# flossjtag.net
KiCad netlist of a schematic drawn in EAGLE
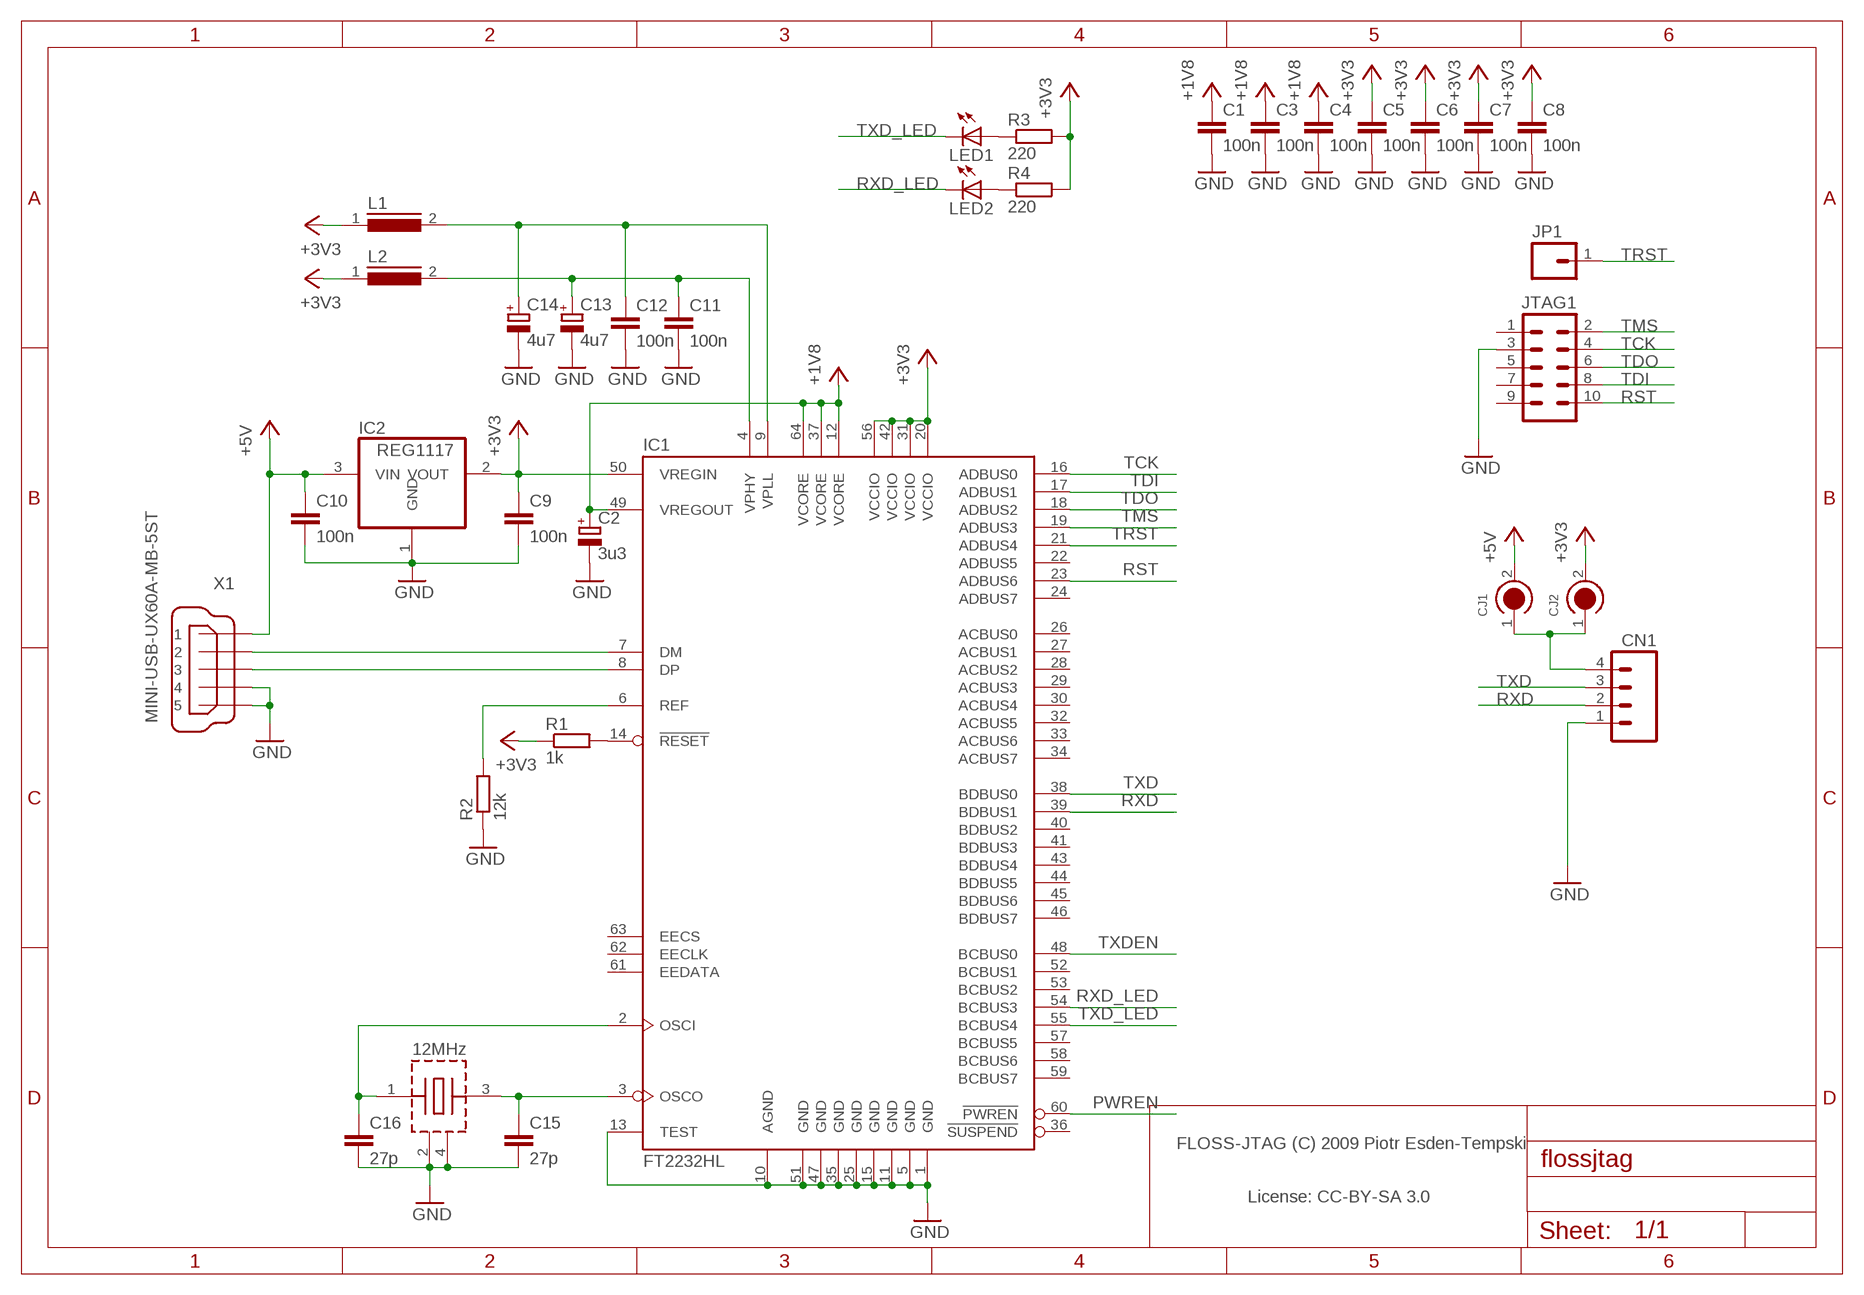
[diagram p0: schematic, sheet 1]

(export (version "E")
  (design (tool "Eeschema 10.0.6"))
  (components
    (comp (ref "C1")
      (value "100n")
      (footprint "eagle-import:C0603")
      (libsource (lib "eagle-import") (part "C-EUC0603"))
    )
    (comp (ref "C2")
      (value "3u3")
      (footprint "eagle-import:A_3216-18R")
      (libsource (lib "eagle-import") (part "CPOL-EUA/3216-18R"))
    )
    (comp (ref "C3")
      (value "100n")
      (footprint "eagle-import:C0603")
      (libsource (lib "eagle-import") (part "C-EUC0603"))
    )
    (comp (ref "C4")
      (value "100n")
      (footprint "eagle-import:C0603")
      (libsource (lib "eagle-import") (part "C-EUC0603"))
    )
    (comp (ref "C5")
      (value "100n")
      (footprint "eagle-import:C0603")
      (libsource (lib "eagle-import") (part "C-EUC0603"))
    )
    (comp (ref "C6")
      (value "100n")
      (footprint "eagle-import:C0603")
      (libsource (lib "eagle-import") (part "C-EUC0603"))
    )
    (comp (ref "C7")
      (value "100n")
      (footprint "eagle-import:C0603")
      (libsource (lib "eagle-import") (part "C-EUC0603"))
    )
    (comp (ref "C8")
      (value "100n")
      (footprint "eagle-import:C0603")
      (libsource (lib "eagle-import") (part "C-EUC0603"))
    )
    (comp (ref "C9")
      (value "100n")
      (footprint "eagle-import:C0603")
      (libsource (lib "eagle-import") (part "C-EUC0603"))
    )
    (comp (ref "C10")
      (value "100n")
      (footprint "eagle-import:C0603")
      (libsource (lib "eagle-import") (part "C-EUC0603"))
    )
    (comp (ref "C11")
      (value "100n")
      (footprint "eagle-import:C0603")
      (libsource (lib "eagle-import") (part "C-EUC0603"))
    )
    (comp (ref "C12")
      (value "100n")
      (footprint "eagle-import:C0603")
      (libsource (lib "eagle-import") (part "C-EUC0603"))
    )
    (comp (ref "C13")
      (value "4u7")
      (footprint "eagle-import:A_3216-18R")
      (libsource (lib "eagle-import") (part "CPOL-EUA/3216-18R"))
    )
    (comp (ref "C14")
      (value "4u7")
      (footprint "eagle-import:A_3216-18R")
      (libsource (lib "eagle-import") (part "CPOL-EUA/3216-18R"))
    )
    (comp (ref "C15")
      (value "27p")
      (footprint "eagle-import:C0603")
      (libsource (lib "eagle-import") (part "C-EUC0603"))
    )
    (comp (ref "C16")
      (value "27p")
      (footprint "eagle-import:C0603")
      (libsource (lib "eagle-import") (part "C-EUC0603"))
    )
    (comp (ref "CJ1")
      (value "CIRC_JMP")
      (footprint "eagle-import:CIRC_JMP")
      (libsource (lib "eagle-import") (part "CIRC_JMP"))
    )
    (comp (ref "CJ2")
      (value "CIRC_JMP")
      (footprint "eagle-import:CIRC_JMP")
      (libsource (lib "eagle-import") (part "CIRC_JMP"))
    )
    (comp (ref "CN1")
      (value "SM04B-SRSS-TB")
      (footprint "eagle-import:SM04B-SRSS-TB")
      (libsource (lib "eagle-import") (part "SM04B-SRSS-TB"))
    )
    (comp (ref "IC1")
      (value "FT2232HL")
      (footprint "eagle-import:LQFP64")
      (libsource (lib "eagle-import") (part "FT2232HL"))
    )
    (comp (ref "IC2")
      (value "REG1117")
      (footprint "eagle-import:SOT223")
      (libsource (lib "eagle-import") (part "REG1117"))
    )
    (comp (ref "JP1")
      (value "PAD-0.06")
      (footprint "eagle-import:PAD-0.06")
      (libsource (lib "eagle-import") (part "PAD-0.06"))
    )
    (comp (ref "JTAG1")
      (value "JTAG-EDGE")
      (footprint "eagle-import:JTAG-EDGE")
      (libsource (lib "eagle-import") (part "JTAG-EDGE"))
    )
    (comp (ref "L1")
      (value "I0603")
      (footprint "eagle-import:R0603")
      (libsource (lib "eagle-import") (part "I0603"))
    )
    (comp (ref "L2")
      (value "I0603")
      (footprint "eagle-import:R0603")
      (libsource (lib "eagle-import") (part "I0603"))
    )
    (comp (ref "LED1")
      (value "LEDCHIP-LED0603")
      (footprint "eagle-import:CHIP-LED0603")
      (libsource (lib "eagle-import") (part "LEDCHIP-LED0603"))
    )
    (comp (ref "LED2")
      (value "LEDCHIP-LED0603")
      (footprint "eagle-import:CHIP-LED0603")
      (libsource (lib "eagle-import") (part "LEDCHIP-LED0603"))
    )
    (comp (ref "R1")
      (value "1k")
      (footprint "eagle-import:R0603")
      (libsource (lib "eagle-import") (part "R-EU_R0603"))
    )
    (comp (ref "R2")
      (value "12k")
      (footprint "eagle-import:R0603")
      (libsource (lib "eagle-import") (part "R-EU_R0603"))
    )
    (comp (ref "R3")
      (value "220")
      (footprint "eagle-import:R0603")
      (libsource (lib "eagle-import") (part "R-EU_R0603"))
    )
    (comp (ref "R4")
      (value "220")
      (footprint "eagle-import:R0603")
      (libsource (lib "eagle-import") (part "R-EU_R0603"))
    )
    (comp (ref "X1")
      (value "MINI-USB-UX60A-MB-5ST")
      (footprint "eagle-import:UX60A-MB-5ST")
      (libsource (lib "eagle-import") (part "MINI-USB-UX60A-MB-5ST"))
    )
    (comp (ref "X3")
      (value "12MHz")
      (footprint "eagle-import:NX3225SA")
      (libsource (lib "eagle-import") (part "NX3225SA"))
    )
  )
  (nets
    (net (code "1") (name "+1V8") (class "Default")
      (node (ref "C1") (pin "1") (pinfunction "1_1") (pintype "passive"))
      (node (ref "C2") (pin "+") (pinfunction "+_+") (pintype "passive"))
      (node (ref "C3") (pin "1") (pinfunction "1_1") (pintype "passive"))
      (node (ref "C4") (pin "1") (pinfunction "1_1") (pintype "passive"))
      (node (ref "IC1") (pin "12") (pinfunction "VCORE_12") (pintype "bidirectional"))
      (node (ref "IC1") (pin "37") (pinfunction "VCORE_37") (pintype "bidirectional"))
      (node (ref "IC1") (pin "49") (pinfunction "VREGOUT_49") (pintype "bidirectional"))
      (node (ref "IC1") (pin "64") (pinfunction "VCORE_64") (pintype "bidirectional"))
    )
    (net (code "2") (name "+3V3") (class "Default")
      (node (ref "C5") (pin "1") (pinfunction "1_1") (pintype "passive"))
      (node (ref "C6") (pin "1") (pinfunction "1_1") (pintype "passive"))
      (node (ref "C7") (pin "1") (pinfunction "1_1") (pintype "passive"))
      (node (ref "C8") (pin "1") (pinfunction "1_1") (pintype "passive"))
      (node (ref "C9") (pin "1") (pinfunction "1_1") (pintype "passive"))
      (node (ref "CJ2") (pin "2") (pinfunction "P$2_2") (pintype "bidirectional"))
      (node (ref "IC1") (pin "20") (pinfunction "VCCIO_20") (pintype "bidirectional"))
      (node (ref "IC1") (pin "31") (pinfunction "VCCIO_31") (pintype "bidirectional"))
      (node (ref "IC1") (pin "42") (pinfunction "VCCIO_42") (pintype "bidirectional"))
      (node (ref "IC1") (pin "50") (pinfunction "VREGIN_50") (pintype "bidirectional"))
      (node (ref "IC1") (pin "56") (pinfunction "VCCIO_56") (pintype "bidirectional"))
      (node (ref "IC2") (pin "2") (pinfunction "VOUT_2") (pintype "output"))
      (node (ref "L1") (pin "1") (pinfunction "1_1") (pintype "passive"))
      (node (ref "L2") (pin "1") (pinfunction "1_1") (pintype "passive"))
      (node (ref "R1") (pin "1") (pinfunction "1_1") (pintype "passive"))
      (node (ref "R3") (pin "2") (pinfunction "2_2") (pintype "passive"))
      (node (ref "R4") (pin "2") (pinfunction "2_2") (pintype "passive"))
    )
    (net (code "3") (name "+5V") (class "Default")
      (node (ref "C10") (pin "1") (pinfunction "1_1") (pintype "passive"))
      (node (ref "CJ1") (pin "2") (pinfunction "P$2_2") (pintype "bidirectional"))
      (node (ref "IC2") (pin "3") (pinfunction "VIN_3") (pintype "input"))
      (node (ref "X1") (pin "1") (pinfunction "1_1") (pintype "input"))
    )
    (net (code "4") (name "/PWREN") (class "Default")
      (node (ref "IC1") (pin "60") (pinfunction "~{PWREN}_60") (pintype "bidirectional"))
    )
    (net (code "5") (name "/RST") (class "Default")
      (node (ref "IC1") (pin "23") (pinfunction "ADBUS6_23") (pintype "bidirectional"))
      (node (ref "JTAG1") (pin "10") (pinfunction "10_10") (pintype "passive"))
    )
    (net (code "6") (name "/RXD") (class "Default")
      (node (ref "CN1") (pin "2") (pinfunction "2_2") (pintype "passive"))
      (node (ref "IC1") (pin "39") (pinfunction "BDBUS1_39") (pintype "bidirectional"))
    )
    (net (code "7") (name "/RXD_LED") (class "Default")
      (node (ref "IC1") (pin "54") (pinfunction "BCBUS3_54") (pintype "bidirectional"))
      (node (ref "LED2") (pin "C") (pinfunction "C_C") (pintype "passive"))
    )
    (net (code "8") (name "/TCK") (class "Default")
      (node (ref "IC1") (pin "16") (pinfunction "ADBUS0_16") (pintype "bidirectional"))
      (node (ref "JTAG1") (pin "4") (pinfunction "4_4") (pintype "passive"))
    )
    (net (code "9") (name "/TDI") (class "Default")
      (node (ref "IC1") (pin "17") (pinfunction "ADBUS1_17") (pintype "bidirectional"))
      (node (ref "JTAG1") (pin "8") (pinfunction "8_8") (pintype "passive"))
    )
    (net (code "10") (name "/TDO") (class "Default")
      (node (ref "IC1") (pin "18") (pinfunction "ADBUS2_18") (pintype "bidirectional"))
      (node (ref "JTAG1") (pin "6") (pinfunction "6_6") (pintype "passive"))
    )
    (net (code "11") (name "/TMS") (class "Default")
      (node (ref "IC1") (pin "19") (pinfunction "ADBUS3_19") (pintype "bidirectional"))
      (node (ref "JTAG1") (pin "2") (pinfunction "2_2") (pintype "passive"))
    )
    (net (code "12") (name "/TRST") (class "Default")
      (node (ref "IC1") (pin "21") (pinfunction "ADBUS4_21") (pintype "bidirectional"))
      (node (ref "JP1") (pin "1") (pinfunction "1_1") (pintype "passive"))
    )
    (net (code "13") (name "/TXD") (class "Default")
      (node (ref "CN1") (pin "3") (pinfunction "3_3") (pintype "passive"))
      (node (ref "IC1") (pin "38") (pinfunction "BDBUS0_38") (pintype "bidirectional"))
    )
    (net (code "14") (name "/TXDEN") (class "Default")
      (node (ref "IC1") (pin "48") (pinfunction "BCBUS0_48") (pintype "bidirectional"))
    )
    (net (code "15") (name "/TXD_LED") (class "Default")
      (node (ref "IC1") (pin "55") (pinfunction "BCBUS4_55") (pintype "bidirectional"))
      (node (ref "LED1") (pin "C") (pinfunction "C_C") (pintype "passive"))
    )
    (net (code "16") (name "GND") (class "Default")
      (node (ref "C1") (pin "2") (pinfunction "2_2") (pintype "passive"))
      (node (ref "C10") (pin "2") (pinfunction "2_2") (pintype "passive"))
      (node (ref "C11") (pin "2") (pinfunction "2_2") (pintype "passive"))
      (node (ref "C12") (pin "2") (pinfunction "2_2") (pintype "passive"))
      (node (ref "C13") (pin "-") (pinfunction "-_-") (pintype "passive"))
      (node (ref "C14") (pin "-") (pinfunction "-_-") (pintype "passive"))
      (node (ref "C15") (pin "2") (pinfunction "2_2") (pintype "passive"))
      (node (ref "C16") (pin "2") (pinfunction "2_2") (pintype "passive"))
      (node (ref "C2") (pin "-") (pinfunction "-_-") (pintype "passive"))
      (node (ref "C3") (pin "2") (pinfunction "2_2") (pintype "passive"))
      (node (ref "C4") (pin "2") (pinfunction "2_2") (pintype "passive"))
      (node (ref "C5") (pin "2") (pinfunction "2_2") (pintype "passive"))
      (node (ref "C6") (pin "2") (pinfunction "2_2") (pintype "passive"))
      (node (ref "C7") (pin "2") (pinfunction "2_2") (pintype "passive"))
      (node (ref "C8") (pin "2") (pinfunction "2_2") (pintype "passive"))
      (node (ref "C9") (pin "2") (pinfunction "2_2") (pintype "passive"))
      (node (ref "CN1") (pin "1") (pinfunction "1_1") (pintype "passive"))
      (node (ref "IC1") (pin "1") (pinfunction "GND_1") (pintype "bidirectional"))
      (node (ref "IC1") (pin "10") (pinfunction "AGND_10") (pintype "bidirectional"))
      (node (ref "IC1") (pin "11") (pinfunction "GND_11") (pintype "bidirectional"))
      (node (ref "IC1") (pin "13") (pinfunction "TEST_13") (pintype "bidirectional"))
      (node (ref "IC1") (pin "15") (pinfunction "GND_15") (pintype "bidirectional"))
      (node (ref "IC1") (pin "25") (pinfunction "GND_25") (pintype "bidirectional"))
      (node (ref "IC1") (pin "35") (pinfunction "GND_35") (pintype "bidirectional"))
      (node (ref "IC1") (pin "47") (pinfunction "GND_47") (pintype "bidirectional"))
      (node (ref "IC1") (pin "5") (pinfunction "GND_5") (pintype "bidirectional"))
      (node (ref "IC1") (pin "51") (pinfunction "GND_51") (pintype "bidirectional"))
      (node (ref "IC2") (pin "1") (pinfunction "GND_1") (pintype "power_in"))
      (node (ref "JTAG1") (pin "3") (pinfunction "3_3") (pintype "passive"))
      (node (ref "R2") (pin "1") (pinfunction "1_1") (pintype "passive"))
      (node (ref "X1") (pin "4") (pinfunction "4_4") (pintype "input"))
      (node (ref "X1") (pin "5") (pinfunction "5_5") (pintype "input"))
      (node (ref "X3") (pin "2") (pinfunction "GND_2") (pintype "bidirectional"))
      (node (ref "X3") (pin "4") (pinfunction "GND_4") (pintype "bidirectional"))
    )
    (net (code "17") (name "Net-(CJ1-P$1)") (class "Default")
      (node (ref "CJ1") (pin "1") (pinfunction "P$1_1") (pintype "bidirectional"))
      (node (ref "CJ2") (pin "1") (pinfunction "P$1_1") (pintype "bidirectional"))
      (node (ref "CN1") (pin "4") (pinfunction "4_4") (pintype "passive"))
    )
    (net (code "18") (name "Net-(IC1-DM)") (class "Default")
      (node (ref "IC1") (pin "7") (pinfunction "DM_7") (pintype "bidirectional"))
      (node (ref "X1") (pin "2") (pinfunction "2_2") (pintype "input"))
    )
    (net (code "19") (name "Net-(IC1-DP)") (class "Default")
      (node (ref "IC1") (pin "8") (pinfunction "DP_8") (pintype "bidirectional"))
      (node (ref "X1") (pin "3") (pinfunction "3_3") (pintype "input"))
    )
    (net (code "20") (name "Net-(IC1-OSCI)") (class "Default")
      (node (ref "C16") (pin "1") (pinfunction "1_1") (pintype "passive"))
      (node (ref "IC1") (pin "2") (pinfunction "OSCI_2") (pintype "bidirectional"))
      (node (ref "X3") (pin "1") (pinfunction "XTAL_1") (pintype "bidirectional"))
    )
    (net (code "21") (name "Net-(IC1-OSCO)") (class "Default")
      (node (ref "C15") (pin "1") (pinfunction "1_1") (pintype "passive"))
      (node (ref "IC1") (pin "3") (pinfunction "OSCO_3") (pintype "bidirectional"))
      (node (ref "X3") (pin "3") (pinfunction "XTAL_3") (pintype "bidirectional"))
    )
    (net (code "22") (name "Net-(IC1-REF)") (class "Default")
      (node (ref "IC1") (pin "6") (pinfunction "REF_6") (pintype "bidirectional"))
      (node (ref "R2") (pin "2") (pinfunction "2_2") (pintype "passive"))
    )
    (net (code "23") (name "Net-(IC1-VPHY)") (class "Default")
      (node (ref "C11") (pin "1") (pinfunction "1_1") (pintype "passive"))
      (node (ref "C13") (pin "+") (pinfunction "+_+") (pintype "passive"))
      (node (ref "IC1") (pin "4") (pinfunction "VPHY_4") (pintype "bidirectional"))
      (node (ref "L2") (pin "2") (pinfunction "2_2") (pintype "passive"))
    )
    (net (code "24") (name "Net-(IC1-VPLL)") (class "Default")
      (node (ref "C12") (pin "1") (pinfunction "1_1") (pintype "passive"))
      (node (ref "C14") (pin "+") (pinfunction "+_+") (pintype "passive"))
      (node (ref "IC1") (pin "9") (pinfunction "VPLL_9") (pintype "bidirectional"))
      (node (ref "L1") (pin "2") (pinfunction "2_2") (pintype "passive"))
    )
    (net (code "25") (name "Net-(IC1-~{RESET})") (class "Default")
      (node (ref "IC1") (pin "14") (pinfunction "~{RESET}_14") (pintype "bidirectional"))
      (node (ref "R1") (pin "2") (pinfunction "2_2") (pintype "passive"))
    )
    (net (code "26") (name "Net-(LED1-PadA)") (class "Default")
      (node (ref "LED1") (pin "A") (pinfunction "A_A") (pintype "passive"))
      (node (ref "R3") (pin "1") (pinfunction "1_1") (pintype "passive"))
    )
    (net (code "27") (name "Net-(LED2-PadA)") (class "Default")
      (node (ref "LED2") (pin "A") (pinfunction "A_A") (pintype "passive"))
      (node (ref "R4") (pin "1") (pinfunction "1_1") (pintype "passive"))
    )
    (net (code "28") (name "unconnected-(IC1-ACBUS0-Pad26)") (class "Default")
      (node (ref "IC1") (pin "26") (pinfunction "ACBUS0_26") (pintype "bidirectional"))
    )
    (net (code "29") (name "unconnected-(IC1-ACBUS1-Pad27)") (class "Default")
      (node (ref "IC1") (pin "27") (pinfunction "ACBUS1_27") (pintype "bidirectional"))
    )
    (net (code "30") (name "unconnected-(IC1-ACBUS2-Pad28)") (class "Default")
      (node (ref "IC1") (pin "28") (pinfunction "ACBUS2_28") (pintype "bidirectional"))
    )
    (net (code "31") (name "unconnected-(IC1-ACBUS3-Pad29)") (class "Default")
      (node (ref "IC1") (pin "29") (pinfunction "ACBUS3_29") (pintype "bidirectional"))
    )
    (net (code "32") (name "unconnected-(IC1-ACBUS4-Pad30)") (class "Default")
      (node (ref "IC1") (pin "30") (pinfunction "ACBUS4_30") (pintype "bidirectional"))
    )
    (net (code "33") (name "unconnected-(IC1-ACBUS5-Pad32)") (class "Default")
      (node (ref "IC1") (pin "32") (pinfunction "ACBUS5_32") (pintype "bidirectional"))
    )
    (net (code "34") (name "unconnected-(IC1-ACBUS6-Pad33)") (class "Default")
      (node (ref "IC1") (pin "33") (pinfunction "ACBUS6_33") (pintype "bidirectional"))
    )
    (net (code "35") (name "unconnected-(IC1-ACBUS7-Pad34)") (class "Default")
      (node (ref "IC1") (pin "34") (pinfunction "ACBUS7_34") (pintype "bidirectional"))
    )
    (net (code "36") (name "unconnected-(IC1-ADBUS5-Pad22)") (class "Default")
      (node (ref "IC1") (pin "22") (pinfunction "ADBUS5_22") (pintype "bidirectional"))
    )
    (net (code "37") (name "unconnected-(IC1-ADBUS7-Pad24)") (class "Default")
      (node (ref "IC1") (pin "24") (pinfunction "ADBUS7_24") (pintype "bidirectional"))
    )
    (net (code "38") (name "unconnected-(IC1-BCBUS1-Pad52)") (class "Default")
      (node (ref "IC1") (pin "52") (pinfunction "BCBUS1_52") (pintype "bidirectional"))
    )
    (net (code "39") (name "unconnected-(IC1-BCBUS2-Pad53)") (class "Default")
      (node (ref "IC1") (pin "53") (pinfunction "BCBUS2_53") (pintype "bidirectional"))
    )
    (net (code "40") (name "unconnected-(IC1-BCBUS5-Pad57)") (class "Default")
      (node (ref "IC1") (pin "57") (pinfunction "BCBUS5_57") (pintype "bidirectional"))
    )
    (net (code "41") (name "unconnected-(IC1-BCBUS6-Pad58)") (class "Default")
      (node (ref "IC1") (pin "58") (pinfunction "BCBUS6_58") (pintype "bidirectional"))
    )
    (net (code "42") (name "unconnected-(IC1-BCBUS7-Pad59)") (class "Default")
      (node (ref "IC1") (pin "59") (pinfunction "BCBUS7_59") (pintype "bidirectional"))
    )
    (net (code "43") (name "unconnected-(IC1-BDBUS2-Pad40)") (class "Default")
      (node (ref "IC1") (pin "40") (pinfunction "BDBUS2_40") (pintype "bidirectional"))
    )
    (net (code "44") (name "unconnected-(IC1-BDBUS3-Pad41)") (class "Default")
      (node (ref "IC1") (pin "41") (pinfunction "BDBUS3_41") (pintype "bidirectional"))
    )
    (net (code "45") (name "unconnected-(IC1-BDBUS4-Pad43)") (class "Default")
      (node (ref "IC1") (pin "43") (pinfunction "BDBUS4_43") (pintype "bidirectional"))
    )
    (net (code "46") (name "unconnected-(IC1-BDBUS5-Pad44)") (class "Default")
      (node (ref "IC1") (pin "44") (pinfunction "BDBUS5_44") (pintype "bidirectional"))
    )
    (net (code "47") (name "unconnected-(IC1-BDBUS6-Pad45)") (class "Default")
      (node (ref "IC1") (pin "45") (pinfunction "BDBUS6_45") (pintype "bidirectional"))
    )
    (net (code "48") (name "unconnected-(IC1-BDBUS7-Pad46)") (class "Default")
      (node (ref "IC1") (pin "46") (pinfunction "BDBUS7_46") (pintype "bidirectional"))
    )
    (net (code "49") (name "unconnected-(IC1-EECLK-Pad62)") (class "Default")
      (node (ref "IC1") (pin "62") (pinfunction "EECLK_62") (pintype "bidirectional"))
    )
    (net (code "50") (name "unconnected-(IC1-EECS-Pad63)") (class "Default")
      (node (ref "IC1") (pin "63") (pinfunction "EECS_63") (pintype "bidirectional"))
    )
    (net (code "51") (name "unconnected-(IC1-EEDATA-Pad61)") (class "Default")
      (node (ref "IC1") (pin "61") (pinfunction "EEDATA_61") (pintype "bidirectional"))
    )
    (net (code "52") (name "unconnected-(IC1-~{SUSPEND}-Pad36)") (class "Default")
      (node (ref "IC1") (pin "36") (pinfunction "~{SUSPEND}_36") (pintype "bidirectional"))
    )
    (net (code "53") (name "unconnected-(JTAG1-Pad1)") (class "Default")
      (node (ref "JTAG1") (pin "1") (pinfunction "1_1") (pintype "passive"))
    )
    (net (code "54") (name "unconnected-(JTAG1-Pad5)") (class "Default")
      (node (ref "JTAG1") (pin "5") (pinfunction "5_5") (pintype "passive"))
    )
    (net (code "55") (name "unconnected-(JTAG1-Pad7)") (class "Default")
      (node (ref "JTAG1") (pin "7") (pinfunction "7_7") (pintype "passive"))
    )
    (net (code "56") (name "unconnected-(JTAG1-Pad9)") (class "Default")
      (node (ref "JTAG1") (pin "9") (pinfunction "9_9") (pintype "passive"))
    )
  )
)
